# 8_Inputs_8_Outputs_Card_schematic.net
KiCad netlist of a schematic drawn in EasyEDA
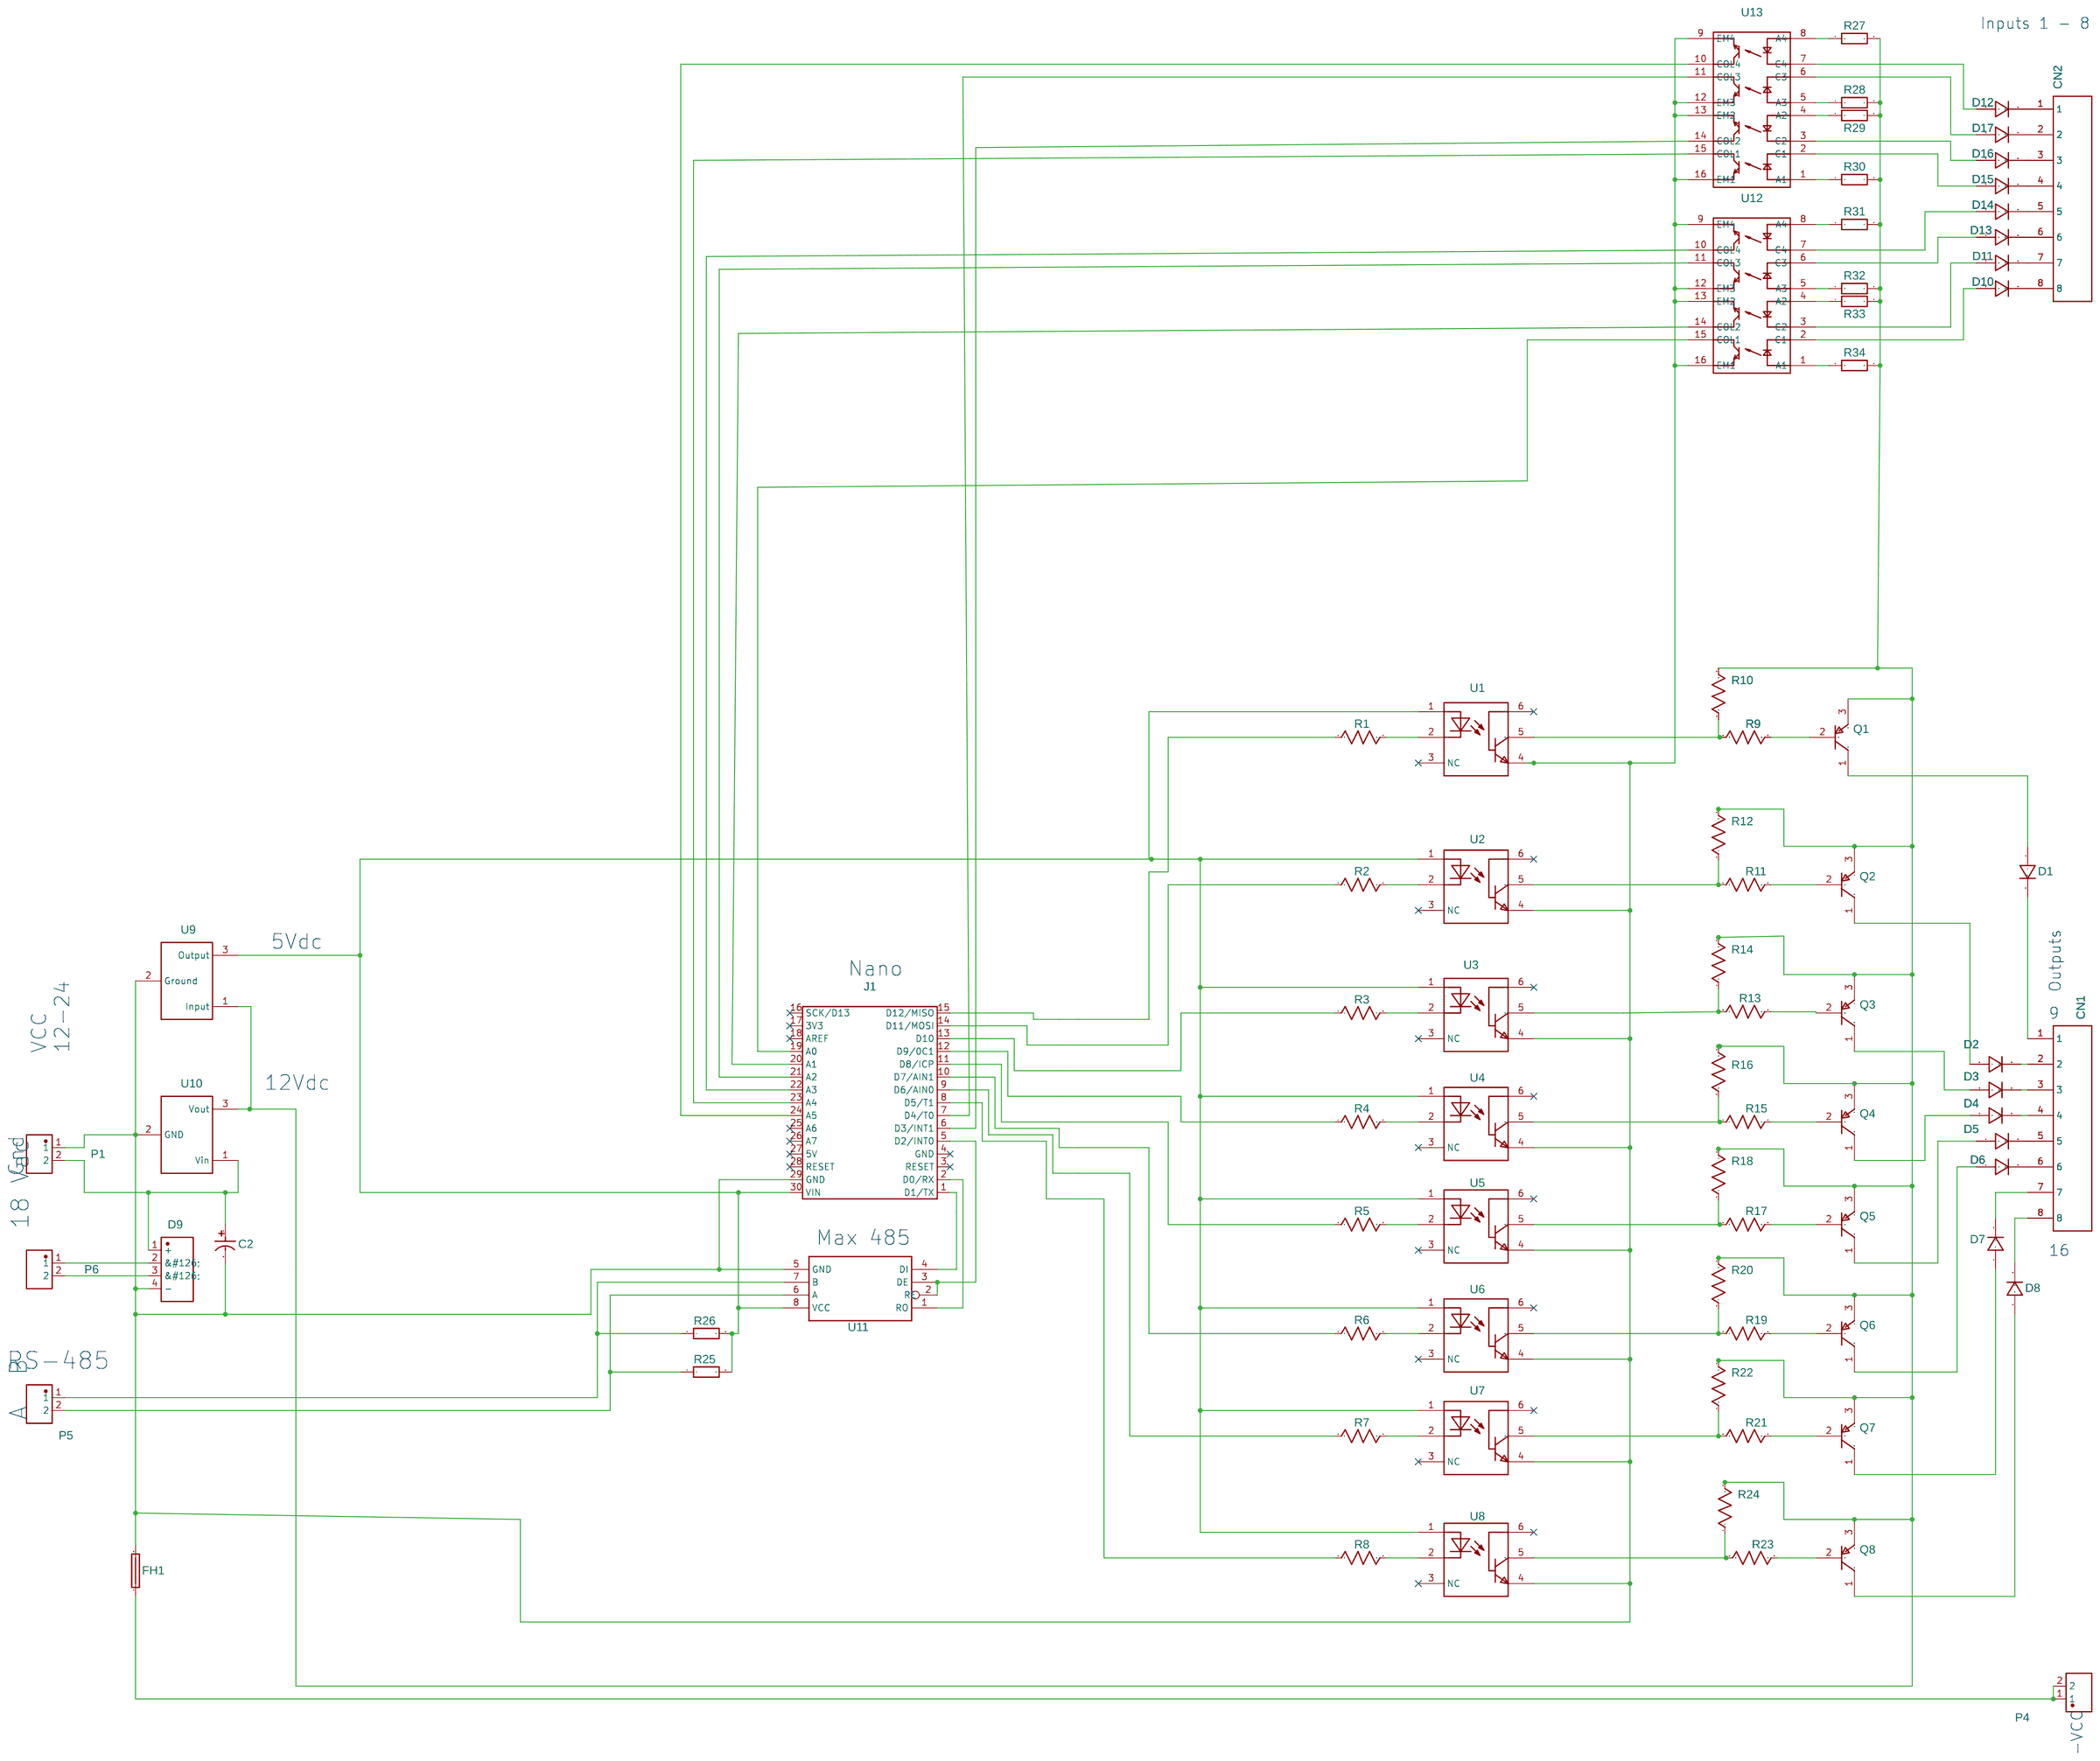
[diagram p0: schematic sheet]

(export (version "E")
  (design (tool "Eeschema 10.0.6"))
  (components
    (comp (ref "C2")
      (value "470uF")
      (fields
        (field (name "BOM_Manufacturer Part") "470uF 100V 16*25")
        (field (name "BOM_Supplier Part") "C72551")
      )
      (libsource (lib "") (part "470uF 100V 16*25"))
    )
    (comp (ref "CN1")
      (value "WJ25C-B-7.62-8P-13-00A")
      (fields (field (name "BOM_Supplier Part") "C49492"))
      (libsource (lib "") (part "Unknown_1530_395"))
    )
    (comp (ref "CN2")
      (value "WJ25C-B-7.62-8P-13-00A")
      (fields (field (name "BOM_Supplier Part") "C49492"))
      (libsource (lib "") (part "Unknown_1530_-330"))
    )
    (comp (ref "D1")
      (value "1N4001")
      (fields (field (name "BOM_Supplier Part") "C169150"))
      (libsource (lib "") (part "Unknown_1510_195"))
    )
    (comp (ref "D2")
      (value "1N4001")
      (fields (field (name "BOM_Supplier Part") "C169150"))
      (libsource (lib "") (part "Unknown_1485_345"))
    )
    (comp (ref "D3")
      (value "1N4001")
      (fields (field (name "BOM_Supplier Part") "C169150"))
      (libsource (lib "") (part "Unknown_1485_365"))
    )
    (comp (ref "D4")
      (value "1N4001")
      (fields (field (name "BOM_Supplier Part") "C169150"))
      (libsource (lib "") (part "Unknown_1485_385"))
    )
    (comp (ref "D5")
      (value "1N4001")
      (fields (field (name "BOM_Supplier Part") "C169150"))
      (libsource (lib "") (part "Unknown_1490_405"))
    )
    (comp (ref "D6")
      (value "1N4001")
      (fields (field (name "BOM_Supplier Part") "C169150"))
      (libsource (lib "") (part "Unknown_1490_425"))
    )
    (comp (ref "D7")
      (value "1N4001")
      (fields (field (name "BOM_Supplier Part") "C169150"))
      (libsource (lib "") (part "Unknown_1485_485"))
    )
    (comp (ref "D8")
      (value "1N4001")
      (fields (field (name "BOM_Supplier Part") "C169150"))
      (libsource (lib "") (part "Unknown_1500_520"))
    )
    (comp (ref "D9")
      (value "D50SB100")
      (fields (field (name "BOM_Supplier Part") "C411148"))
      (libsource (lib "") (part "Unknown_60_505"))
    )
    (comp (ref "D10")
      (value "1N4001")
      (fields (field (name "BOM_Supplier Part") "C169150"))
      (libsource (lib "") (part "Unknown_1490_-260"))
    )
    (comp (ref "D11")
      (value "1N4001")
      (fields (field (name "BOM_Supplier Part") "C169150"))
      (libsource (lib "") (part "Unknown_1490_-280"))
    )
    (comp (ref "D12")
      (value "1N4001")
      (fields (field (name "BOM_Supplier Part") "C169150"))
      (libsource (lib "") (part "Unknown_1490_-400"))
    )
    (comp (ref "D13")
      (value "1N4001")
      (fields (field (name "BOM_Supplier Part") "C169150"))
      (libsource (lib "") (part "Unknown_1490_-300"))
    )
    (comp (ref "D14")
      (value "1N4001")
      (fields (field (name "BOM_Supplier Part") "C169150"))
      (libsource (lib "") (part "Unknown_1490_-320"))
    )
    (comp (ref "D15")
      (value "1N4001")
      (fields (field (name "BOM_Supplier Part") "C169150"))
      (libsource (lib "") (part "Unknown_1490_-340"))
    )
    (comp (ref "D16")
      (value "1N4001")
      (fields (field (name "BOM_Supplier Part") "C169150"))
      (libsource (lib "") (part "Unknown_1490_-360"))
    )
    (comp (ref "D17")
      (value "1N4001")
      (fields (field (name "BOM_Supplier Part") "C169150"))
      (libsource (lib "") (part "Unknown_1490_-380"))
    )
    (comp (ref "FH1")
      (value "64600001003")
      (fields (field (name "BOM_Supplier Part") "C206887"))
      (libsource (lib "") (part "Unknown_35_740"))
    )
    (comp (ref "J1") (value "Arduino_Nano_Header") (libsource (lib "") (part "Unknown_605_375")))
    (comp (ref "P1")
      (value "WJ25C-B-2P")
      (fields (field (name "BOM_Supplier Part") "C8422"))
      (libsource (lib "") (part "Unknown_-40_415"))
    )
    (comp (ref "P4")
      (value "WJ25C-B-2P")
      (fields (field (name "BOM_Supplier Part") "C8422"))
      (libsource (lib "") (part "Unknown_1550_835"))
    )
    (comp (ref "P5")
      (value "WJ25C-B-2P")
      (fields (field (name "BOM_Supplier Part") "C8422"))
      (libsource (lib "") (part "Unknown_-40_610"))
    )
    (comp (ref "P6")
      (value "WJ25C-B-2P")
      (fields (field (name "BOM_Supplier Part") "C8422"))
      (libsource (lib "") (part "Unknown_-40_505"))
    )
    (comp (ref "Q1")
      (value "2N4033")
      (fields (field (name "BOM_Supplier Part") "610-2N4033"))
      (libsource (lib "") (part "Unknown_1355_90"))
    )
    (comp (ref "Q2")
      (value "2N4033")
      (fields (field (name "BOM_Supplier Part") "610-2N4033"))
      (libsource (lib "") (part "Unknown_1360_205"))
    )
    (comp (ref "Q3")
      (value "2N4033")
      (fields (field (name "BOM_Supplier Part") "610-2N4033"))
      (libsource (lib "") (part "Unknown_1360_305"))
    )
    (comp (ref "Q4")
      (value "2N4033")
      (fields (field (name "BOM_Supplier Part") "610-2N4033"))
      (libsource (lib "") (part "Unknown_1360_390"))
    )
    (comp (ref "Q5")
      (value "2N4033")
      (fields (field (name "BOM_Supplier Part") "610-2N4033"))
      (libsource (lib "") (part "Unknown_1360_470"))
    )
    (comp (ref "Q6")
      (value "2N4033")
      (fields (field (name "BOM_Supplier Part") "610-2N4033"))
      (libsource (lib "") (part "Unknown_1360_555"))
    )
    (comp (ref "Q7")
      (value "2N4033")
      (fields (field (name "BOM_Supplier Part") "610-2N4033"))
      (libsource (lib "") (part "Unknown_1360_635"))
    )
    (comp (ref "Q8")
      (value "2N4033")
      (fields (field (name "BOM_Supplier Part") "610-2N4033"))
      (libsource (lib "") (part "Unknown_1360_730"))
    )
    (comp (ref "R1")
      (value "1k")
      (fields
        (field (name "BOM_Manufacturer Part") "MFR0W4F1001A50")
        (field (name "BOM_Supplier Part") "C57435")
      )
      (libsource (lib "") (part "Res_AXIAL-0.3(1/8W)_US"))
    )
    (comp (ref "R2")
      (value "1k")
      (fields
        (field (name "BOM_Manufacturer Part") "MFR0W4F1001A50")
        (field (name "BOM_Supplier Part") "C57435")
      )
      (libsource (lib "") (part "Res_AXIAL-0.3(1/8W)_US"))
    )
    (comp (ref "R3")
      (value "1k")
      (fields
        (field (name "BOM_Manufacturer Part") "MFR0W4F1001A50")
        (field (name "BOM_Supplier Part") "C57435")
      )
      (libsource (lib "") (part "Res_AXIAL-0.3(1/8W)_US"))
    )
    (comp (ref "R4")
      (value "1k")
      (fields
        (field (name "BOM_Manufacturer Part") "MFR0W4F1001A50")
        (field (name "BOM_Supplier Part") "C57435")
      )
      (libsource (lib "") (part "Res_AXIAL-0.3(1/8W)_US"))
    )
    (comp (ref "R5")
      (value "1k")
      (fields
        (field (name "BOM_Manufacturer Part") "MFR0W4F1001A50")
        (field (name "BOM_Supplier Part") "C57435")
      )
      (libsource (lib "") (part "Res_AXIAL-0.3(1/8W)_US"))
    )
    (comp (ref "R6")
      (value "1k")
      (fields
        (field (name "BOM_Manufacturer Part") "MFR0W4F1001A50")
        (field (name "BOM_Supplier Part") "C57435")
      )
      (libsource (lib "") (part "Res_AXIAL-0.3(1/8W)_US"))
    )
    (comp (ref "R7")
      (value "1k")
      (fields
        (field (name "BOM_Manufacturer Part") "MFR0W4F1001A50")
        (field (name "BOM_Supplier Part") "C57435")
      )
      (libsource (lib "") (part "Res_AXIAL-0.3(1/8W)_US"))
    )
    (comp (ref "R8")
      (value "1k")
      (fields
        (field (name "BOM_Manufacturer Part") "MFR0W4F1001A50")
        (field (name "BOM_Supplier Part") "C57435")
      )
      (libsource (lib "") (part "Res_AXIAL-0.3(1/8W)_US"))
    )
    (comp (ref "R9")
      (value "1k")
      (fields
        (field (name "BOM_Manufacturer Part") "MFR0W4F1001A50")
        (field (name "BOM_Supplier Part") "C57435")
      )
      (libsource (lib "") (part "Res_AXIAL-0.3(1/8W)_US"))
    )
    (comp (ref "R10")
      (value "1k")
      (fields
        (field (name "BOM_Manufacturer Part") "MFR0W4F1001A50")
        (field (name "BOM_Supplier Part") "C57435")
      )
      (libsource (lib "") (part "Res_AXIAL-0.3(1/8W)_US_1"))
    )
    (comp (ref "R11")
      (value "1k")
      (fields
        (field (name "BOM_Manufacturer Part") "MFR0W4F1001A50")
        (field (name "BOM_Supplier Part") "C57435")
      )
      (libsource (lib "") (part "Res_AXIAL-0.3(1/8W)_US"))
    )
    (comp (ref "R12")
      (value "1k")
      (fields
        (field (name "BOM_Manufacturer Part") "MFR0W4F1001A50")
        (field (name "BOM_Supplier Part") "C57435")
      )
      (libsource (lib "") (part "Res_AXIAL-0.3(1/8W)_US_1"))
    )
    (comp (ref "R13")
      (value "1k")
      (fields
        (field (name "BOM_Manufacturer Part") "MFR0W4F1001A50")
        (field (name "BOM_Supplier Part") "C57435")
      )
      (libsource (lib "") (part "Res_AXIAL-0.3(1/8W)_US"))
    )
    (comp (ref "R14")
      (value "1k")
      (fields
        (field (name "BOM_Manufacturer Part") "MFR0W4F1001A50")
        (field (name "BOM_Supplier Part") "C57435")
      )
      (libsource (lib "") (part "Res_AXIAL-0.3(1/8W)_US_1"))
    )
    (comp (ref "R15")
      (value "1k")
      (fields
        (field (name "BOM_Manufacturer Part") "MFR0W4F1001A50")
        (field (name "BOM_Supplier Part") "C57435")
      )
      (libsource (lib "") (part "Res_AXIAL-0.3(1/8W)_US"))
    )
    (comp (ref "R16")
      (value "1k")
      (fields
        (field (name "BOM_Manufacturer Part") "MFR0W4F1001A50")
        (field (name "BOM_Supplier Part") "C57435")
      )
      (libsource (lib "") (part "Res_AXIAL-0.3(1/8W)_US_1"))
    )
    (comp (ref "R17")
      (value "1k")
      (fields
        (field (name "BOM_Manufacturer Part") "MFR0W4F1001A50")
        (field (name "BOM_Supplier Part") "C57435")
      )
      (libsource (lib "") (part "Res_AXIAL-0.3(1/8W)_US"))
    )
    (comp (ref "R18")
      (value "1k")
      (fields
        (field (name "BOM_Manufacturer Part") "MFR0W4F1001A50")
        (field (name "BOM_Supplier Part") "C57435")
      )
      (libsource (lib "") (part "Res_AXIAL-0.3(1/8W)_US_1"))
    )
    (comp (ref "R19")
      (value "1k")
      (fields
        (field (name "BOM_Manufacturer Part") "MFR0W4F1001A50")
        (field (name "BOM_Supplier Part") "C57435")
      )
      (libsource (lib "") (part "Res_AXIAL-0.3(1/8W)_US"))
    )
    (comp (ref "R20")
      (value "1k")
      (fields
        (field (name "BOM_Manufacturer Part") "MFR0W4F1001A50")
        (field (name "BOM_Supplier Part") "C57435")
      )
      (libsource (lib "") (part "Res_AXIAL-0.3(1/8W)_US_1"))
    )
    (comp (ref "R21")
      (value "1k")
      (fields
        (field (name "BOM_Manufacturer Part") "MFR0W4F1001A50")
        (field (name "BOM_Supplier Part") "C57435")
      )
      (libsource (lib "") (part "Res_AXIAL-0.3(1/8W)_US"))
    )
    (comp (ref "R22")
      (value "1k")
      (fields
        (field (name "BOM_Manufacturer Part") "MFR0W4F1001A50")
        (field (name "BOM_Supplier Part") "C57435")
      )
      (libsource (lib "") (part "Res_AXIAL-0.3(1/8W)_US_1"))
    )
    (comp (ref "R23")
      (value "1k")
      (fields
        (field (name "BOM_Manufacturer Part") "MFR0W4F1001A50")
        (field (name "BOM_Supplier Part") "C57435")
      )
      (libsource (lib "") (part "Res_AXIAL-0.3(1/8W)_US"))
    )
    (comp (ref "R24")
      (value "1k")
      (fields
        (field (name "BOM_Manufacturer Part") "MFR0W4F1001A50")
        (field (name "BOM_Supplier Part") "C57435")
      )
      (libsource (lib "") (part "Res_AXIAL-0.3(1/8W)_US_1"))
    )
    (comp (ref "R25")
      (value "10K")
      (fields
        (field (name "BOM_Manufacturer Part") "CFR0W4J0103A50")
        (field (name "BOM_Supplier Part") "C61299")
      )
      (libsource (lib "") (part "CFR0W4J0103A50"))
    )
    (comp (ref "R26")
      (value "10K")
      (fields
        (field (name "BOM_Manufacturer Part") "CFR0W4J0103A50")
        (field (name "BOM_Supplier Part") "C61299")
      )
      (libsource (lib "") (part "CFR0W4J0103A50"))
    )
    (comp (ref "R27")
      (value "220")
      (fields
        (field (name "BOM_Manufacturer Part") "CFR0W4J0221A50")
        (field (name "BOM_Supplier Part") "C61289")
      )
      (libsource (lib "") (part "CFR0W4J0221A50"))
    )
    (comp (ref "R28")
      (value "220")
      (fields
        (field (name "BOM_Manufacturer Part") "CFR0W4J0221A50")
        (field (name "BOM_Supplier Part") "C61289")
      )
      (libsource (lib "") (part "CFR0W4J0221A50"))
    )
    (comp (ref "R29")
      (value "220")
      (fields
        (field (name "BOM_Manufacturer Part") "CFR0W4J0221A50")
        (field (name "BOM_Supplier Part") "C61289")
      )
      (libsource (lib "") (part "CFR0W4J0221A50"))
    )
    (comp (ref "R30")
      (value "220")
      (fields
        (field (name "BOM_Manufacturer Part") "CFR0W4J0221A50")
        (field (name "BOM_Supplier Part") "C61289")
      )
      (libsource (lib "") (part "CFR0W4J0221A50"))
    )
    (comp (ref "R31")
      (value "220")
      (fields
        (field (name "BOM_Manufacturer Part") "CFR0W4J0221A50")
        (field (name "BOM_Supplier Part") "C61289")
      )
      (libsource (lib "") (part "CFR0W4J0221A50"))
    )
    (comp (ref "R32")
      (value "220")
      (fields
        (field (name "BOM_Manufacturer Part") "CFR0W4J0221A50")
        (field (name "BOM_Supplier Part") "C61289")
      )
      (libsource (lib "") (part "CFR0W4J0221A50"))
    )
    (comp (ref "R33")
      (value "220")
      (fields
        (field (name "BOM_Manufacturer Part") "CFR0W4J0221A50")
        (field (name "BOM_Supplier Part") "C61289")
      )
      (libsource (lib "") (part "CFR0W4J0221A50"))
    )
    (comp (ref "R34")
      (value "220")
      (fields
        (field (name "BOM_Manufacturer Part") "CFR0W4J0221A50")
        (field (name "BOM_Supplier Part") "C61289")
      )
      (libsource (lib "") (part "CFR0W4J0221A50"))
    )
    (comp (ref "U1")
      (value "4N25M")
      (fields (field (name "BOM_Supplier Part") "C5241"))
      (libsource (lib "") (part "Unknown_1080_90"))
    )
    (comp (ref "U2")
      (value "4N25M")
      (fields (field (name "BOM_Supplier Part") "C5241"))
      (libsource (lib "") (part "Unknown_1080_205"))
    )
    (comp (ref "U3")
      (value "4N25M")
      (fields (field (name "BOM_Supplier Part") "C5241"))
      (libsource (lib "") (part "Unknown_1080_305"))
    )
    (comp (ref "U4")
      (value "4N25M")
      (fields (field (name "BOM_Supplier Part") "C5241"))
      (libsource (lib "") (part "Unknown_1080_390"))
    )
    (comp (ref "U5")
      (value "4N25M")
      (fields (field (name "BOM_Supplier Part") "C5241"))
      (libsource (lib "") (part "Unknown_1080_470"))
    )
    (comp (ref "U6")
      (value "4N25M")
      (fields (field (name "BOM_Supplier Part") "C5241"))
      (libsource (lib "") (part "Unknown_1080_555"))
    )
    (comp (ref "U7")
      (value "4N25M")
      (fields (field (name "BOM_Supplier Part") "C5241"))
      (libsource (lib "") (part "Unknown_1080_635"))
    )
    (comp (ref "U8")
      (value "4N25M")
      (fields (field (name "BOM_Supplier Part") "C5241"))
      (libsource (lib "") (part "Unknown_1080_730"))
    )
    (comp (ref "U9")
      (value "MC7805BTG")
      (fields (field (name "BOM_Supplier Part") "C45385"))
      (libsource (lib "") (part "Unknown_75_280"))
    )
    (comp (ref "U10")
      (value "CJ7812")
      (fields (field (name "BOM_Supplier Part") "C77894"))
      (libsource (lib "") (part "Unknown_75_400"))
    )
    (comp (ref "U11") (value "MAX485DIL") (libsource (lib "") (part "Unknown_600_520")))
    (comp (ref "U12")
      (value "ILQ2")
      (fields (field (name "BOM_Supplier Part") "C145338"))
      (libsource (lib "") (part "ILQ2"))
    )
    (comp (ref "U13")
      (value "ILQ2")
      (fields (field (name "BOM_Supplier Part") "C145338"))
      (libsource (lib "") (part "ILQ2"))
    )
  )
  (nets
    (net (code "1") (name "Net-(CN1-Pad1)") (class "Default")
      (node (ref "CN1") (pin "1") (pinfunction "1_1") (pintype "input"))
      (node (ref "D1") (pin "2") (pinfunction "2_2") (pintype "unspecified"))
    )
    (net (code "2") (name "Net-(CN1-Pad2)") (class "Default")
      (node (ref "CN1") (pin "2") (pinfunction "2_2") (pintype "input"))
      (node (ref "D2") (pin "2") (pinfunction "2_2") (pintype "unspecified"))
    )
    (net (code "3") (name "Net-(CN1-Pad3)") (class "Default")
      (node (ref "CN1") (pin "3") (pinfunction "3_3") (pintype "input"))
      (node (ref "D3") (pin "2") (pinfunction "2_2") (pintype "unspecified"))
    )
    (net (code "4") (name "Net-(CN1-Pad4)") (class "Default")
      (node (ref "CN1") (pin "4") (pinfunction "4_4") (pintype "input"))
      (node (ref "D4") (pin "2") (pinfunction "2_2") (pintype "unspecified"))
    )
    (net (code "5") (name "Net-(CN1-Pad5)") (class "Default")
      (node (ref "CN1") (pin "5") (pinfunction "5_5") (pintype "input"))
      (node (ref "D5") (pin "2") (pinfunction "2_2") (pintype "unspecified"))
    )
    (net (code "6") (name "Net-(CN1-Pad6)") (class "Default")
      (node (ref "CN1") (pin "6") (pinfunction "6_6") (pintype "input"))
      (node (ref "D6") (pin "2") (pinfunction "2_2") (pintype "unspecified"))
    )
    (net (code "7") (name "Net-(CN1-Pad7)") (class "Default")
      (node (ref "CN1") (pin "7") (pinfunction "7_7") (pintype "input"))
      (node (ref "D7") (pin "2") (pinfunction "2_2") (pintype "unspecified"))
    )
    (net (code "8") (name "Net-(CN1-Pad8)") (class "Default")
      (node (ref "CN1") (pin "8") (pinfunction "8_8") (pintype "input"))
      (node (ref "D8") (pin "2") (pinfunction "2_2") (pintype "unspecified"))
    )
    (net (code "9") (name "Net-(CN2-Pad1)") (class "Default")
      (node (ref "CN2") (pin "1") (pinfunction "1_1") (pintype "input"))
      (node (ref "D12") (pin "2") (pinfunction "2_2") (pintype "unspecified"))
    )
    (net (code "10") (name "Net-(CN2-Pad2)") (class "Default")
      (node (ref "CN2") (pin "2") (pinfunction "2_2") (pintype "input"))
      (node (ref "D17") (pin "2") (pinfunction "2_2") (pintype "unspecified"))
    )
    (net (code "11") (name "Net-(CN2-Pad3)") (class "Default")
      (node (ref "CN2") (pin "3") (pinfunction "3_3") (pintype "input"))
      (node (ref "D16") (pin "2") (pinfunction "2_2") (pintype "unspecified"))
    )
    (net (code "12") (name "Net-(CN2-Pad4)") (class "Default")
      (node (ref "CN2") (pin "4") (pinfunction "4_4") (pintype "input"))
      (node (ref "D15") (pin "2") (pinfunction "2_2") (pintype "unspecified"))
    )
    (net (code "13") (name "Net-(CN2-Pad5)") (class "Default")
      (node (ref "CN2") (pin "5") (pinfunction "5_5") (pintype "input"))
      (node (ref "D14") (pin "2") (pinfunction "2_2") (pintype "unspecified"))
    )
    (net (code "14") (name "Net-(CN2-Pad6)") (class "Default")
      (node (ref "CN2") (pin "6") (pinfunction "6_6") (pintype "input"))
      (node (ref "D13") (pin "2") (pinfunction "2_2") (pintype "unspecified"))
    )
    (net (code "15") (name "Net-(CN2-Pad7)") (class "Default")
      (node (ref "CN2") (pin "7") (pinfunction "7_7") (pintype "input"))
      (node (ref "D11") (pin "2") (pinfunction "2_2") (pintype "unspecified"))
    )
    (net (code "16") (name "Net-(CN2-Pad8)") (class "Default")
      (node (ref "CN2") (pin "8") (pinfunction "8_8") (pintype "input"))
      (node (ref "D10") (pin "2") (pinfunction "2_2") (pintype "unspecified"))
    )
    (net (code "17") (name "Net-(D9-&#126;-Pad2)") (class "Default")
      (node (ref "D9") (pin "2") (pinfunction "&#126;_2") (pintype "unspecified"))
      (node (ref "P6") (pin "1") (pinfunction "1_1") (pintype "unspecified"))
    )
    (net (code "18") (name "Net-(D9-&#126;-Pad3)") (class "Default")
      (node (ref "D9") (pin "3") (pinfunction "&#126;_3") (pintype "unspecified"))
      (node (ref "P6") (pin "2") (pinfunction "2_2") (pintype "unspecified"))
    )
    (net (code "19") (name "Net-(D9-+)") (class "Default")
      (node (ref "C2") (pin "1") (pinfunction "1_1") (pintype "input"))
      (node (ref "D9") (pin "1") (pinfunction "+_1") (pintype "unspecified"))
      (node (ref "P1") (pin "2") (pinfunction "2_2") (pintype "unspecified"))
      (node (ref "U10") (pin "1") (pinfunction "Vin_1") (pintype "unspecified"))
    )
    (net (code "20") (name "Net-(D9--)") (class "Default")
      (node (ref "C2") (pin "2") (pinfunction "2_2") (pintype "input"))
      (node (ref "D9") (pin "4") (pinfunction "-_4") (pintype "unspecified"))
      (node (ref "FH1") (pin "2") (pinfunction "2_2") (pintype "unspecified"))
      (node (ref "J1") (pin "29") (pinfunction "GND_29") (pintype "unspecified"))
      (node (ref "P1") (pin "1") (pinfunction "1_1") (pintype "unspecified"))
      (node (ref "U1") (pin "4") (pinfunction "4_4") (pintype "unspecified"))
      (node (ref "U10") (pin "2") (pinfunction "GND_2") (pintype "unspecified"))
      (node (ref "U11") (pin "5") (pinfunction "GND_5") (pintype "unspecified"))
      (node (ref "U12") (pin "12") (pinfunction "EM3_12") (pintype "unspecified"))
      (node (ref "U12") (pin "13") (pinfunction "EM2_13") (pintype "unspecified"))
      (node (ref "U12") (pin "16") (pinfunction "EM1_16") (pintype "unspecified"))
      (node (ref "U12") (pin "9") (pinfunction "EM4_9") (pintype "unspecified"))
      (node (ref "U13") (pin "12") (pinfunction "EM3_12") (pintype "unspecified"))
      (node (ref "U13") (pin "13") (pinfunction "EM2_13") (pintype "unspecified"))
      (node (ref "U13") (pin "16") (pinfunction "EM1_16") (pintype "unspecified"))
      (node (ref "U13") (pin "9") (pinfunction "EM4_9") (pintype "unspecified"))
      (node (ref "U2") (pin "4") (pinfunction "4_4") (pintype "unspecified"))
      (node (ref "U3") (pin "4") (pinfunction "4_4") (pintype "unspecified"))
      (node (ref "U4") (pin "4") (pinfunction "4_4") (pintype "unspecified"))
      (node (ref "U5") (pin "4") (pinfunction "4_4") (pintype "unspecified"))
      (node (ref "U6") (pin "4") (pinfunction "4_4") (pintype "unspecified"))
      (node (ref "U7") (pin "4") (pinfunction "4_4") (pintype "unspecified"))
      (node (ref "U8") (pin "4") (pinfunction "4_4") (pintype "unspecified"))
      (node (ref "U9") (pin "2") (pinfunction "Ground_2") (pintype "unspecified"))
    )
    (net (code "21") (name "Net-(FH1-Pad1)") (class "Default")
      (node (ref "FH1") (pin "1") (pinfunction "1_1") (pintype "unspecified"))
      (node (ref "P4") (pin "1") (pinfunction "1_1") (pintype "unspecified"))
      (node (ref "P4") (pin "2") (pinfunction "2_2") (pintype "unspecified"))
    )
    (net (code "22") (name "Net-(J1-A0)") (class "Default")
      (node (ref "J1") (pin "19") (pinfunction "A0_19") (pintype "unspecified"))
      (node (ref "U12") (pin "15") (pinfunction "COL1_15") (pintype "unspecified"))
    )
    (net (code "23") (name "Net-(J1-A1)") (class "Default")
      (node (ref "J1") (pin "20") (pinfunction "A1_20") (pintype "unspecified"))
      (node (ref "U12") (pin "14") (pinfunction "COL2_14") (pintype "unspecified"))
    )
    (net (code "24") (name "Net-(J1-A2)") (class "Default")
      (node (ref "J1") (pin "21") (pinfunction "A2_21") (pintype "unspecified"))
      (node (ref "U12") (pin "11") (pinfunction "COL3_11") (pintype "unspecified"))
    )
    (net (code "25") (name "Net-(J1-A3)") (class "Default")
      (node (ref "J1") (pin "22") (pinfunction "A3_22") (pintype "unspecified"))
      (node (ref "U12") (pin "10") (pinfunction "COL4_10") (pintype "unspecified"))
    )
    (net (code "26") (name "Net-(J1-A4)") (class "Default")
      (node (ref "J1") (pin "23") (pinfunction "A4_23") (pintype "unspecified"))
      (node (ref "U13") (pin "15") (pinfunction "COL1_15") (pintype "unspecified"))
    )
    (net (code "27") (name "Net-(J1-A5)") (class "Default")
      (node (ref "J1") (pin "24") (pinfunction "A5_24") (pintype "unspecified"))
      (node (ref "U13") (pin "10") (pinfunction "COL4_10") (pintype "unspecified"))
    )
    (net (code "28") (name "Net-(J1-D0{slash}RX)") (class "Default")
      (node (ref "J1") (pin "2") (pinfunction "D0/RX_2") (pintype "unspecified"))
      (node (ref "U11") (pin "1") (pinfunction "RO_1") (pintype "unspecified"))
    )
    (net (code "29") (name "Net-(J1-D1{slash}TX)") (class "Default")
      (node (ref "J1") (pin "1") (pinfunction "D1/TX_1") (pintype "unspecified"))
      (node (ref "U11") (pin "4") (pinfunction "DI_4") (pintype "unspecified"))
    )
    (net (code "30") (name "Net-(J1-D2{slash}INT0)") (class "Default")
      (node (ref "J1") (pin "5") (pinfunction "D2/INT0_5") (pintype "unspecified"))
      (node (ref "U11") (pin "2") (pinfunction "RE_2") (pintype "unspecified"))
      (node (ref "U11") (pin "3") (pinfunction "DE_3") (pintype "unspecified"))
    )
    (net (code "31") (name "Net-(J1-D3{slash}INT1)") (class "Default")
      (node (ref "J1") (pin "6") (pinfunction "D3/INT1_6") (pintype "unspecified"))
      (node (ref "U13") (pin "14") (pinfunction "COL2_14") (pintype "unspecified"))
    )
    (net (code "32") (name "Net-(J1-D4{slash}T0)") (class "Default")
      (node (ref "J1") (pin "7") (pinfunction "D4/T0_7") (pintype "unspecified"))
      (node (ref "U13") (pin "11") (pinfunction "COL3_11") (pintype "unspecified"))
    )
    (net (code "33") (name "Net-(J1-D5{slash}T1)") (class "Default")
      (node (ref "J1") (pin "8") (pinfunction "D5/T1_8") (pintype "unspecified"))
      (node (ref "R8") (pin "1") (pinfunction "1_1") (pintype "unspecified"))
    )
    (net (code "34") (name "Net-(J1-D6{slash}AIN0)") (class "Default")
      (node (ref "J1") (pin "9") (pinfunction "D6/AIN0_9") (pintype "unspecified"))
      (node (ref "R7") (pin "1") (pinfunction "1_1") (pintype "unspecified"))
    )
    (net (code "35") (name "Net-(J1-D7{slash}AIN1)") (class "Default")
      (node (ref "J1") (pin "10") (pinfunction "D7/AIN1_10") (pintype "unspecified"))
      (node (ref "R6") (pin "1") (pinfunction "1_1") (pintype "unspecified"))
    )
    (net (code "36") (name "Net-(J1-D8{slash}ICP)") (class "Default")
      (node (ref "J1") (pin "11") (pinfunction "D8/ICP_11") (pintype "unspecified"))
      (node (ref "R5") (pin "1") (pinfunction "1_1") (pintype "unspecified"))
    )
    (net (code "37") (name "Net-(J1-D9{slash}0C1)") (class "Default")
      (node (ref "J1") (pin "12") (pinfunction "D9/0C1_12") (pintype "unspecified"))
      (node (ref "R4") (pin "1") (pinfunction "1_1") (pintype "unspecified"))
    )
    (net (code "38") (name "Net-(J1-D10)") (class "Default")
      (node (ref "J1") (pin "13") (pinfunction "D10_13") (pintype "unspecified"))
      (node (ref "R3") (pin "1") (pinfunction "1_1") (pintype "unspecified"))
    )
    (net (code "39") (name "Net-(J1-D11{slash}MOSI)") (class "Default")
      (node (ref "J1") (pin "14") (pinfunction "D11/MOSI_14") (pintype "unspecified"))
      (node (ref "R2") (pin "1") (pinfunction "1_1") (pintype "unspecified"))
    )
    (net (code "40") (name "Net-(J1-D12{slash}MISO)") (class "Default")
      (node (ref "J1") (pin "15") (pinfunction "D12/MISO_15") (pintype "unspecified"))
      (node (ref "R1") (pin "1") (pinfunction "1_1") (pintype "unspecified"))
    )
    (net (code "41") (name "Net-(J1-VIN)") (class "Default")
      (node (ref "J1") (pin "30") (pinfunction "VIN_30") (pintype "unspecified"))
      (node (ref "R25") (pin "2") (pinfunction "2_2") (pintype "input"))
      (node (ref "R26") (pin "2") (pinfunction "2_2") (pintype "input"))
      (node (ref "U1") (pin "1") (pinfunction "1_1") (pintype "unspecified"))
      (node (ref "U11") (pin "8") (pinfunction "VCC_8") (pintype "unspecified"))
      (node (ref "U2") (pin "1") (pinfunction "1_1") (pintype "unspecified"))
      (node (ref "U3") (pin "1") (pinfunction "1_1") (pintype "unspecified"))
      (node (ref "U4") (pin "1") (pinfunction "1_1") (pintype "unspecified"))
      (node (ref "U5") (pin "1") (pinfunction "1_1") (pintype "unspecified"))
      (node (ref "U6") (pin "1") (pinfunction "1_1") (pintype "unspecified"))
      (node (ref "U7") (pin "1") (pinfunction "1_1") (pintype "unspecified"))
      (node (ref "U8") (pin "1") (pinfunction "1_1") (pintype "unspecified"))
      (node (ref "U9") (pin "3") (pinfunction "Output_3") (pintype "unspecified"))
    )
    (net (code "42") (name "Net-(Q1-B)") (class "Default")
      (node (ref "Q1") (pin "2") (pinfunction "B_2") (pintype "unspecified"))
      (node (ref "R9") (pin "2") (pinfunction "2_2") (pintype "unspecified"))
    )
    (net (code "43") (name "Net-(Q1-C)") (class "Default")
      (node (ref "D1") (pin "1") (pinfunction "1_1") (pintype "unspecified"))
      (node (ref "Q1") (pin "1") (pinfunction "C_1") (pintype "unspecified"))
    )
    (net (code "44") (name "Net-(Q1-E)") (class "Default")
      (node (ref "Q1") (pin "3") (pinfunction "E_3") (pintype "unspecified"))
      (node (ref "Q2") (pin "3") (pinfunction "E_3") (pintype "unspecified"))
      (node (ref "Q3") (pin "3") (pinfunction "E_3") (pintype "unspecified"))
      (node (ref "Q4") (pin "3") (pinfunction "E_3") (pintype "unspecified"))
      (node (ref "Q5") (pin "3") (pinfunction "E_3") (pintype "unspecified"))
      (node (ref "Q6") (pin "3") (pinfunction "E_3") (pintype "unspecified"))
      (node (ref "Q7") (pin "3") (pinfunction "E_3") (pintype "unspecified"))
      (node (ref "Q8") (pin "3") (pinfunction "E_3") (pintype "unspecified"))
      (node (ref "R10") (pin "2") (pinfunction "2_2") (pintype "unspecified"))
      (node (ref "R12") (pin "2") (pinfunction "2_2") (pintype "unspecified"))
      (node (ref "R14") (pin "2") (pinfunction "2_2") (pintype "unspecified"))
      (node (ref "R16") (pin "2") (pinfunction "2_2") (pintype "unspecified"))
      (node (ref "R18") (pin "2") (pinfunction "2_2") (pintype "unspecified"))
      (node (ref "R20") (pin "2") (pinfunction "2_2") (pintype "unspecified"))
      (node (ref "R22") (pin "2") (pinfunction "2_2") (pintype "unspecified"))
      (node (ref "R24") (pin "2") (pinfunction "2_2") (pintype "unspecified"))
      (node (ref "R27") (pin "2") (pinfunction "2_2") (pintype "input"))
      (node (ref "R28") (pin "2") (pinfunction "2_2") (pintype "input"))
      (node (ref "R29") (pin "2") (pinfunction "2_2") (pintype "input"))
      (node (ref "R30") (pin "2") (pinfunction "2_2") (pintype "input"))
      (node (ref "R31") (pin "2") (pinfunction "2_2") (pintype "input"))
      (node (ref "R32") (pin "2") (pinfunction "2_2") (pintype "input"))
      (node (ref "R33") (pin "2") (pinfunction "2_2") (pintype "input"))
      (node (ref "R34") (pin "2") (pinfunction "2_2") (pintype "input"))
      (node (ref "U10") (pin "3") (pinfunction "Vout_3") (pintype "unspecified"))
      (node (ref "U9") (pin "1") (pinfunction "Input_1") (pintype "unspecified"))
    )
    (net (code "45") (name "Net-(Q2-B)") (class "Default")
      (node (ref "Q2") (pin "2") (pinfunction "B_2") (pintype "unspecified"))
      (node (ref "R11") (pin "2") (pinfunction "2_2") (pintype "unspecified"))
    )
    (net (code "46") (name "Net-(Q2-C)") (class "Default")
      (node (ref "D2") (pin "1") (pinfunction "1_1") (pintype "unspecified"))
      (node (ref "Q2") (pin "1") (pinfunction "C_1") (pintype "unspecified"))
    )
    (net (code "47") (name "Net-(Q3-B)") (class "Default")
      (node (ref "Q3") (pin "2") (pinfunction "B_2") (pintype "unspecified"))
      (node (ref "R13") (pin "2") (pinfunction "2_2") (pintype "unspecified"))
    )
    (net (code "48") (name "Net-(Q3-C)") (class "Default")
      (node (ref "D3") (pin "1") (pinfunction "1_1") (pintype "unspecified"))
      (node (ref "Q3") (pin "1") (pinfunction "C_1") (pintype "unspecified"))
    )
    (net (code "49") (name "Net-(Q4-B)") (class "Default")
      (node (ref "Q4") (pin "2") (pinfunction "B_2") (pintype "unspecified"))
      (node (ref "R15") (pin "2") (pinfunction "2_2") (pintype "unspecified"))
    )
    (net (code "50") (name "Net-(Q4-C)") (class "Default")
      (node (ref "D4") (pin "1") (pinfunction "1_1") (pintype "unspecified"))
      (node (ref "Q4") (pin "1") (pinfunction "C_1") (pintype "unspecified"))
    )
    (net (code "51") (name "Net-(Q5-B)") (class "Default")
      (node (ref "Q5") (pin "2") (pinfunction "B_2") (pintype "unspecified"))
      (node (ref "R17") (pin "2") (pinfunction "2_2") (pintype "unspecified"))
    )
    (net (code "52") (name "Net-(Q5-C)") (class "Default")
      (node (ref "D5") (pin "1") (pinfunction "1_1") (pintype "unspecified"))
      (node (ref "Q5") (pin "1") (pinfunction "C_1") (pintype "unspecified"))
    )
    (net (code "53") (name "Net-(Q6-B)") (class "Default")
      (node (ref "Q6") (pin "2") (pinfunction "B_2") (pintype "unspecified"))
      (node (ref "R19") (pin "2") (pinfunction "2_2") (pintype "unspecified"))
    )
    (net (code "54") (name "Net-(Q6-C)") (class "Default")
      (node (ref "D6") (pin "1") (pinfunction "1_1") (pintype "unspecified"))
      (node (ref "Q6") (pin "1") (pinfunction "C_1") (pintype "unspecified"))
    )
    (net (code "55") (name "Net-(Q7-B)") (class "Default")
      (node (ref "Q7") (pin "2") (pinfunction "B_2") (pintype "unspecified"))
      (node (ref "R21") (pin "2") (pinfunction "2_2") (pintype "unspecified"))
    )
    (net (code "56") (name "Net-(Q7-C)") (class "Default")
      (node (ref "D7") (pin "1") (pinfunction "1_1") (pintype "unspecified"))
      (node (ref "Q7") (pin "1") (pinfunction "C_1") (pintype "unspecified"))
    )
    (net (code "57") (name "Net-(Q8-B)") (class "Default")
      (node (ref "Q8") (pin "2") (pinfunction "B_2") (pintype "unspecified"))
      (node (ref "R23") (pin "2") (pinfunction "2_2") (pintype "unspecified"))
    )
    (net (code "58") (name "Net-(Q8-C)") (class "Default")
      (node (ref "D8") (pin "1") (pinfunction "1_1") (pintype "unspecified"))
      (node (ref "Q8") (pin "1") (pinfunction "C_1") (pintype "unspecified"))
    )
    (net (code "59") (name "Net-(R1-Pad2)") (class "Default")
      (node (ref "R1") (pin "2") (pinfunction "2_2") (pintype "unspecified"))
      (node (ref "U1") (pin "2") (pinfunction "2_2") (pintype "unspecified"))
    )
    (net (code "60") (name "Net-(R2-Pad2)") (class "Default")
      (node (ref "R2") (pin "2") (pinfunction "2_2") (pintype "unspecified"))
      (node (ref "U2") (pin "2") (pinfunction "2_2") (pintype "unspecified"))
    )
    (net (code "61") (name "Net-(R3-Pad2)") (class "Default")
      (node (ref "R3") (pin "2") (pinfunction "2_2") (pintype "unspecified"))
      (node (ref "U3") (pin "2") (pinfunction "2_2") (pintype "unspecified"))
    )
    (net (code "62") (name "Net-(R4-Pad2)") (class "Default")
      (node (ref "R4") (pin "2") (pinfunction "2_2") (pintype "unspecified"))
      (node (ref "U4") (pin "2") (pinfunction "2_2") (pintype "unspecified"))
    )
    (net (code "63") (name "Net-(R5-Pad2)") (class "Default")
      (node (ref "R5") (pin "2") (pinfunction "2_2") (pintype "unspecified"))
      (node (ref "U5") (pin "2") (pinfunction "2_2") (pintype "unspecified"))
    )
    (net (code "64") (name "Net-(R6-Pad2)") (class "Default")
      (node (ref "R6") (pin "2") (pinfunction "2_2") (pintype "unspecified"))
      (node (ref "U6") (pin "2") (pinfunction "2_2") (pintype "unspecified"))
    )
    (net (code "65") (name "Net-(R7-Pad2)") (class "Default")
      (node (ref "R7") (pin "2") (pinfunction "2_2") (pintype "unspecified"))
      (node (ref "U7") (pin "2") (pinfunction "2_2") (pintype "unspecified"))
    )
    (net (code "66") (name "Net-(R8-Pad2)") (class "Default")
      (node (ref "R8") (pin "2") (pinfunction "2_2") (pintype "unspecified"))
      (node (ref "U8") (pin "2") (pinfunction "2_2") (pintype "unspecified"))
    )
    (net (code "67") (name "Net-(R10-Pad1)") (class "Default")
      (node (ref "R10") (pin "1") (pinfunction "1_1") (pintype "unspecified"))
      (node (ref "R9") (pin "1") (pinfunction "1_1") (pintype "unspecified"))
      (node (ref "U1") (pin "5") (pinfunction "5_5") (pintype "unspecified"))
    )
    (net (code "68") (name "Net-(R11-Pad1)") (class "Default")
      (node (ref "R11") (pin "1") (pinfunction "1_1") (pintype "unspecified"))
      (node (ref "R12") (pin "1") (pinfunction "1_1") (pintype "unspecified"))
      (node (ref "U2") (pin "5") (pinfunction "5_5") (pintype "unspecified"))
    )
    (net (code "69") (name "Net-(R13-Pad1)") (class "Default")
      (node (ref "R13") (pin "1") (pinfunction "1_1") (pintype "unspecified"))
      (node (ref "R14") (pin "1") (pinfunction "1_1") (pintype "unspecified"))
      (node (ref "U3") (pin "5") (pinfunction "5_5") (pintype "unspecified"))
    )
    (net (code "70") (name "Net-(R15-Pad1)") (class "Default")
      (node (ref "R15") (pin "1") (pinfunction "1_1") (pintype "unspecified"))
      (node (ref "R16") (pin "1") (pinfunction "1_1") (pintype "unspecified"))
      (node (ref "U4") (pin "5") (pinfunction "5_5") (pintype "unspecified"))
    )
    (net (code "71") (name "Net-(R17-Pad1)") (class "Default")
      (node (ref "R17") (pin "1") (pinfunction "1_1") (pintype "unspecified"))
      (node (ref "R18") (pin "1") (pinfunction "1_1") (pintype "unspecified"))
      (node (ref "U5") (pin "5") (pinfunction "5_5") (pintype "unspecified"))
    )
    (net (code "72") (name "Net-(R19-Pad1)") (class "Default")
      (node (ref "R19") (pin "1") (pinfunction "1_1") (pintype "unspecified"))
      (node (ref "R20") (pin "1") (pinfunction "1_1") (pintype "unspecified"))
      (node (ref "U6") (pin "5") (pinfunction "5_5") (pintype "unspecified"))
    )
    (net (code "73") (name "Net-(R21-Pad1)") (class "Default")
      (node (ref "R21") (pin "1") (pinfunction "1_1") (pintype "unspecified"))
      (node (ref "R22") (pin "1") (pinfunction "1_1") (pintype "unspecified"))
      (node (ref "U7") (pin "5") (pinfunction "5_5") (pintype "unspecified"))
    )
    (net (code "74") (name "Net-(R23-Pad1)") (class "Default")
      (node (ref "R23") (pin "1") (pinfunction "1_1") (pintype "unspecified"))
      (node (ref "R24") (pin "1") (pinfunction "1_1") (pintype "unspecified"))
      (node (ref "U8") (pin "5") (pinfunction "5_5") (pintype "unspecified"))
    )
    (net (code "75") (name "Net-(U11-A)") (class "Default")
      (node (ref "P5") (pin "2") (pinfunction "2_2") (pintype "unspecified"))
      (node (ref "R25") (pin "1") (pinfunction "1_1") (pintype "input"))
      (node (ref "U11") (pin "6") (pinfunction "A_6") (pintype "unspecified"))
    )
    (net (code "76") (name "Net-(U11-B)") (class "Default")
      (node (ref "P5") (pin "1") (pinfunction "1_1") (pintype "unspecified"))
      (node (ref "R26") (pin "1") (pinfunction "1_1") (pintype "input"))
      (node (ref "U11") (pin "7") (pinfunction "B_7") (pintype "unspecified"))
    )
    (net (code "77") (name "Net-(U12-A1)") (class "Default")
      (node (ref "R34") (pin "1") (pinfunction "1_1") (pintype "input"))
      (node (ref "U12") (pin "1") (pinfunction "A1_1") (pintype "unspecified"))
    )
    (net (code "78") (name "Net-(U12-A2)") (class "Default")
      (node (ref "R33") (pin "1") (pinfunction "1_1") (pintype "input"))
      (node (ref "U12") (pin "4") (pinfunction "A2_4") (pintype "unspecified"))
    )
    (net (code "79") (name "Net-(U12-A3)") (class "Default")
      (node (ref "R32") (pin "1") (pinfunction "1_1") (pintype "input"))
      (node (ref "U12") (pin "5") (pinfunction "A3_5") (pintype "unspecified"))
    )
    (net (code "80") (name "Net-(U12-A4)") (class "Default")
      (node (ref "R31") (pin "1") (pinfunction "1_1") (pintype "input"))
      (node (ref "U12") (pin "8") (pinfunction "A4_8") (pintype "unspecified"))
    )
    (net (code "81") (name "Net-(U12-C1)") (class "Default")
      (node (ref "D10") (pin "1") (pinfunction "1_1") (pintype "unspecified"))
      (node (ref "U12") (pin "2") (pinfunction "C1_2") (pintype "unspecified"))
    )
    (net (code "82") (name "Net-(U12-C2)") (class "Default")
      (node (ref "D11") (pin "1") (pinfunction "1_1") (pintype "unspecified"))
      (node (ref "U12") (pin "3") (pinfunction "C2_3") (pintype "unspecified"))
    )
    (net (code "83") (name "Net-(U12-C3)") (class "Default")
      (node (ref "D13") (pin "1") (pinfunction "1_1") (pintype "unspecified"))
      (node (ref "U12") (pin "6") (pinfunction "C3_6") (pintype "unspecified"))
    )
    (net (code "84") (name "Net-(U12-C4)") (class "Default")
      (node (ref "D14") (pin "1") (pinfunction "1_1") (pintype "unspecified"))
      (node (ref "U12") (pin "7") (pinfunction "C4_7") (pintype "unspecified"))
    )
    (net (code "85") (name "Net-(U13-A1)") (class "Default")
      (node (ref "R30") (pin "1") (pinfunction "1_1") (pintype "input"))
      (node (ref "U13") (pin "1") (pinfunction "A1_1") (pintype "unspecified"))
    )
    (net (code "86") (name "Net-(U13-A2)") (class "Default")
      (node (ref "R29") (pin "1") (pinfunction "1_1") (pintype "input"))
      (node (ref "U13") (pin "4") (pinfunction "A2_4") (pintype "unspecified"))
    )
    (net (code "87") (name "Net-(U13-A3)") (class "Default")
      (node (ref "R28") (pin "1") (pinfunction "1_1") (pintype "input"))
      (node (ref "U13") (pin "5") (pinfunction "A3_5") (pintype "unspecified"))
    )
    (net (code "88") (name "Net-(U13-A4)") (class "Default")
      (node (ref "R27") (pin "1") (pinfunction "1_1") (pintype "input"))
      (node (ref "U13") (pin "8") (pinfunction "A4_8") (pintype "unspecified"))
    )
    (net (code "89") (name "Net-(U13-C1)") (class "Default")
      (node (ref "D15") (pin "1") (pinfunction "1_1") (pintype "unspecified"))
      (node (ref "U13") (pin "2") (pinfunction "C1_2") (pintype "unspecified"))
    )
    (net (code "90") (name "Net-(U13-C2)") (class "Default")
      (node (ref "D16") (pin "1") (pinfunction "1_1") (pintype "unspecified"))
      (node (ref "U13") (pin "3") (pinfunction "C2_3") (pintype "unspecified"))
    )
    (net (code "91") (name "Net-(U13-C3)") (class "Default")
      (node (ref "D17") (pin "1") (pinfunction "1_1") (pintype "unspecified"))
      (node (ref "U13") (pin "6") (pinfunction "C3_6") (pintype "unspecified"))
    )
    (net (code "92") (name "Net-(U13-C4)") (class "Default")
      (node (ref "D12") (pin "1") (pinfunction "1_1") (pintype "unspecified"))
      (node (ref "U13") (pin "7") (pinfunction "C4_7") (pintype "unspecified"))
    )
    (net (code "93") (name "unconnected-(J1-3V3-Pad17)") (class "Default")
      (node (ref "J1") (pin "17") (pinfunction "3V3_17") (pintype "unspecified+no_connect"))
    )
    (net (code "94") (name "unconnected-(J1-5V-Pad27)") (class "Default")
      (node (ref "J1") (pin "27") (pinfunction "5V_27") (pintype "unspecified+no_connect"))
    )
    (net (code "95") (name "unconnected-(J1-A6-Pad25)") (class "Default")
      (node (ref "J1") (pin "25") (pinfunction "A6_25") (pintype "unspecified+no_connect"))
    )
    (net (code "96") (name "unconnected-(J1-A7-Pad26)") (class "Default")
      (node (ref "J1") (pin "26") (pinfunction "A7_26") (pintype "unspecified+no_connect"))
    )
    (net (code "97") (name "unconnected-(J1-AREF-Pad18)") (class "Default")
      (node (ref "J1") (pin "18") (pinfunction "AREF_18") (pintype "unspecified+no_connect"))
    )
    (net (code "98") (name "unconnected-(J1-GND-Pad4)") (class "Default")
      (node (ref "J1") (pin "4") (pinfunction "GND_4") (pintype "unspecified+no_connect"))
    )
    (net (code "99") (name "unconnected-(J1-RESET-Pad3)") (class "Default")
      (node (ref "J1") (pin "3") (pinfunction "RESET_3") (pintype "unspecified+no_connect"))
    )
    (net (code "100") (name "unconnected-(J1-RESET-Pad28)") (class "Default")
      (node (ref "J1") (pin "28") (pinfunction "RESET_28") (pintype "unspecified+no_connect"))
    )
    (net (code "101") (name "unconnected-(J1-SCK{slash}D13-Pad16)") (class "Default")
      (node (ref "J1") (pin "16") (pinfunction "SCK/D13_16") (pintype "unspecified+no_connect"))
    )
    (net (code "102") (name "unconnected-(U1-NC-Pad3)") (class "Default")
      (node (ref "U1") (pin "3") (pinfunction "NC_3") (pintype "unspecified+no_connect"))
    )
    (net (code "103") (name "unconnected-(U1-Pad6)") (class "Default")
      (node (ref "U1") (pin "6") (pinfunction "6_6") (pintype "unspecified+no_connect"))
    )
    (net (code "104") (name "unconnected-(U2-NC-Pad3)") (class "Default")
      (node (ref "U2") (pin "3") (pinfunction "NC_3") (pintype "unspecified+no_connect"))
    )
    (net (code "105") (name "unconnected-(U2-Pad6)") (class "Default")
      (node (ref "U2") (pin "6") (pinfunction "6_6") (pintype "unspecified+no_connect"))
    )
    (net (code "106") (name "unconnected-(U3-NC-Pad3)") (class "Default")
      (node (ref "U3") (pin "3") (pinfunction "NC_3") (pintype "unspecified+no_connect"))
    )
    (net (code "107") (name "unconnected-(U3-Pad6)") (class "Default")
      (node (ref "U3") (pin "6") (pinfunction "6_6") (pintype "unspecified+no_connect"))
    )
    (net (code "108") (name "unconnected-(U4-NC-Pad3)") (class "Default")
      (node (ref "U4") (pin "3") (pinfunction "NC_3") (pintype "unspecified+no_connect"))
    )
    (net (code "109") (name "unconnected-(U4-Pad6)") (class "Default")
      (node (ref "U4") (pin "6") (pinfunction "6_6") (pintype "unspecified+no_connect"))
    )
    (net (code "110") (name "unconnected-(U5-NC-Pad3)") (class "Default")
      (node (ref "U5") (pin "3") (pinfunction "NC_3") (pintype "unspecified+no_connect"))
    )
    (net (code "111") (name "unconnected-(U5-Pad6)") (class "Default")
      (node (ref "U5") (pin "6") (pinfunction "6_6") (pintype "unspecified+no_connect"))
    )
    (net (code "112") (name "unconnected-(U6-NC-Pad3)") (class "Default")
      (node (ref "U6") (pin "3") (pinfunction "NC_3") (pintype "unspecified+no_connect"))
    )
    (net (code "113") (name "unconnected-(U6-Pad6)") (class "Default")
      (node (ref "U6") (pin "6") (pinfunction "6_6") (pintype "unspecified+no_connect"))
    )
    (net (code "114") (name "unconnected-(U7-NC-Pad3)") (class "Default")
      (node (ref "U7") (pin "3") (pinfunction "NC_3") (pintype "unspecified+no_connect"))
    )
    (net (code "115") (name "unconnected-(U7-Pad6)") (class "Default")
      (node (ref "U7") (pin "6") (pinfunction "6_6") (pintype "unspecified+no_connect"))
    )
    (net (code "116") (name "unconnected-(U8-NC-Pad3)") (class "Default")
      (node (ref "U8") (pin "3") (pinfunction "NC_3") (pintype "unspecified+no_connect"))
    )
    (net (code "117") (name "unconnected-(U8-Pad6)") (class "Default")
      (node (ref "U8") (pin "6") (pinfunction "6_6") (pintype "unspecified+no_connect"))
    )
  )
)
